# 14-MT7688AN_USB-PCIe.net
KiCad netlist of a schematic drawn in Altium Designer
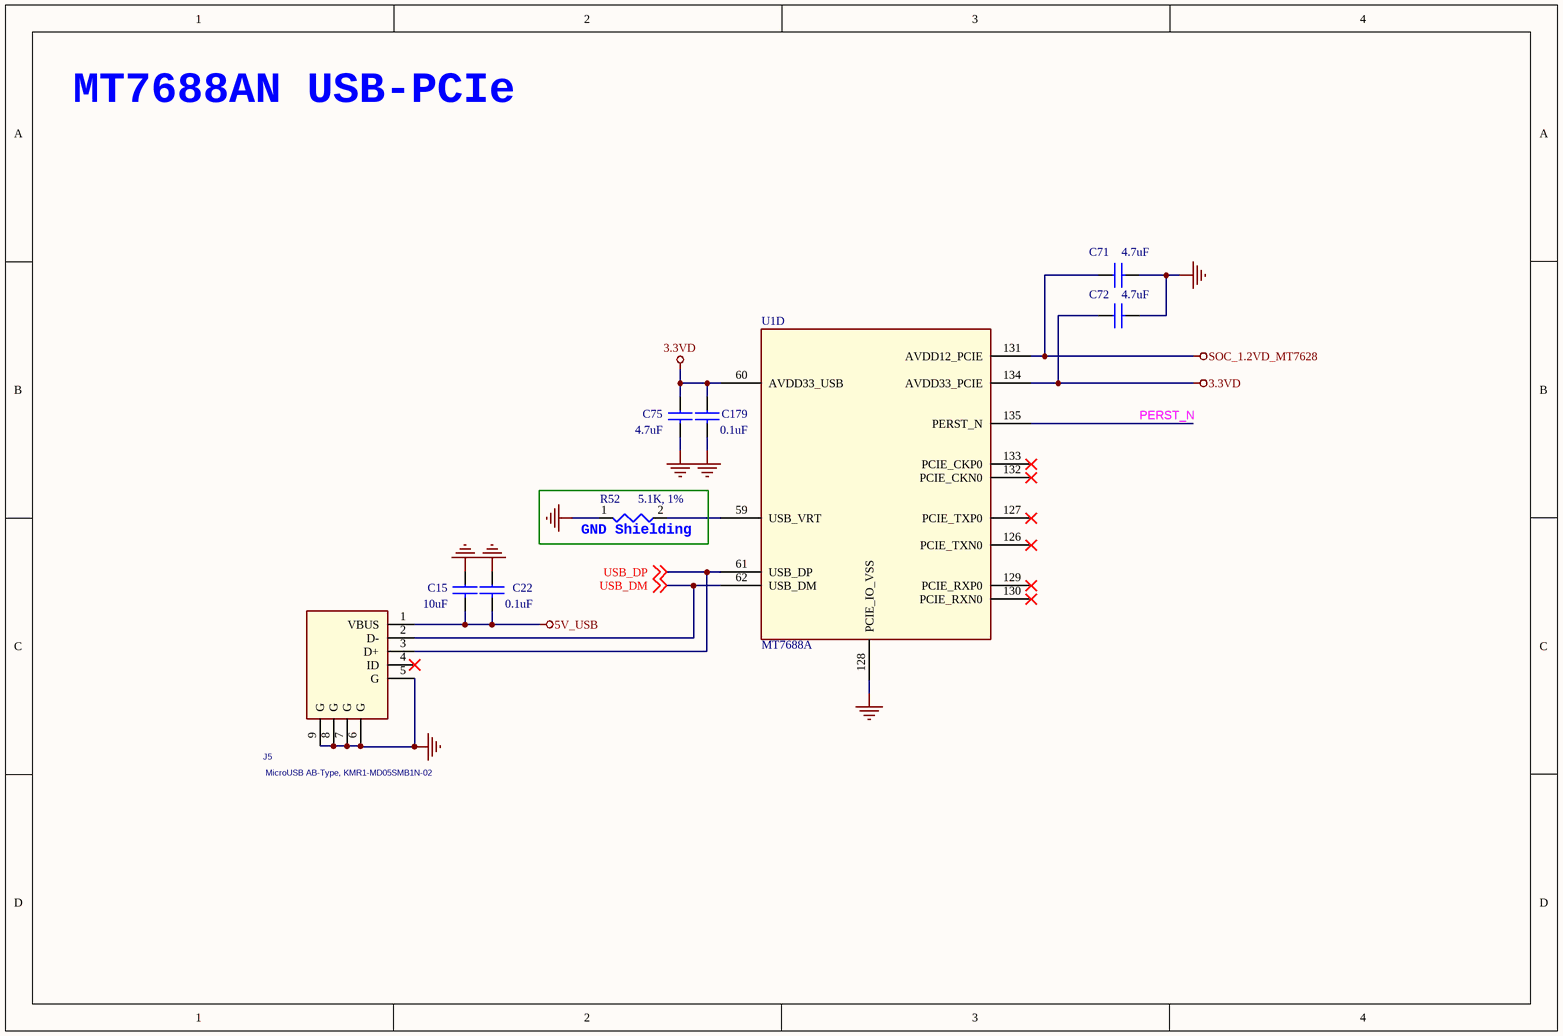
[diagram p0: 14-MT7688AN USB-PCIe.SchDoc]

(export (version "E")
  (design (tool "Eeschema 10.0.6"))
  (components
    (comp (ref "C15")
      (value "10uF")
      (footprint "RLC 0402 M35")
      (libsource (lib "LinkIt Air+ (EK-7688AM+)") (part "CAP NP"))
    )
    (comp (ref "C22")
      (value "0.1uF")
      (footprint "RLC 0201 M35")
      (libsource (lib "LinkIt Air+ (EK-7688AM+)") (part "CAP NP"))
    )
    (comp (ref "C71")
      (value "4.7uF")
      (footprint "RLC 0402 M35")
      (libsource (lib "LinkIt Air+ (EK-7688AM+)") (part "CAP NP"))
    )
    (comp (ref "C72")
      (value "4.7uF")
      (footprint "RLC 0402 M35")
      (libsource (lib "LinkIt Air+ (EK-7688AM+)") (part "CAP NP"))
    )
    (comp (ref "C75")
      (value "4.7uF")
      (footprint "RLC 0402 M35")
      (libsource (lib "LinkIt Air+ (EK-7688AM+)") (part "CAP NP"))
    )
    (comp (ref "C179")
      (value "0.1uF")
      (footprint "RLC 0201 M35")
      (libsource (lib "LinkIt Air+ (EK-7688AM+)") (part "CAP NP"))
    )
    (comp (ref "J5")
      (value "MicroUSB AB-Type, KMR1-MD05SMB1N-02")
      (footprint "MicroUSB-AB")
      (description "MicroUSB AB-Type")
      (fields (field (name "MANUFACTURER") "CUI Inc."))
      (libsource (lib "LinkIt Air+ (EK-7688AM+)") (part "Micro USB TYPE-AB"))
    )
    (comp (ref "R52")
      (value "5.1K, 1%")
      (footprint "RLC 0201 M35")
      (libsource (lib "LinkIt Air+ (EK-7688AM+)") (part "RES/0402_3"))
    )
    (comp (ref "U1")
      (value "MT7688A")
      (footprint "MT7628AN$2F$DRQFN156$2F$SMD$2F$P0.5$2F$12X12")
      (libsource (lib "LinkIt Air+ (EK-7688AM+)") (part "MT7620N-n_26"))
    )
  )
  (nets
    (net (code "1") (name "/PERST_N") (class "Default")
      (node (ref "U1") (pin "135") (pinfunction "PERST_N_135") (pintype "passive"))
    )
    (net (code "2") (name "3.3VD") (class "Default")
      (node (ref "C179") (pin "1") (pinfunction "1_1") (pintype "passive"))
      (node (ref "C72") (pin "1") (pinfunction "1_1") (pintype "passive"))
      (node (ref "C75") (pin "1") (pinfunction "1_1") (pintype "passive"))
      (node (ref "U1") (pin "134") (pinfunction "AVDD33_PCIE_134") (pintype "power_in"))
      (node (ref "U1") (pin "60") (pinfunction "AVDD33_USB_60") (pintype "passive"))
    )
    (net (code "3") (name "5V_USB") (class "Default")
      (node (ref "C15") (pin "2") (pinfunction "2_2") (pintype "passive"))
      (node (ref "C22") (pin "2") (pinfunction "2_2") (pintype "passive"))
      (node (ref "J5") (pin "1") (pinfunction "VBUS_1") (pintype "passive"))
    )
    (net (code "4") (name "GND") (class "Default")
      (node (ref "C15") (pin "1") (pinfunction "1_1") (pintype "passive"))
      (node (ref "C179") (pin "2") (pinfunction "2_2") (pintype "passive"))
      (node (ref "C22") (pin "1") (pinfunction "1_1") (pintype "passive"))
      (node (ref "C71") (pin "2") (pinfunction "2_2") (pintype "passive"))
      (node (ref "C72") (pin "2") (pinfunction "2_2") (pintype "passive"))
      (node (ref "C75") (pin "2") (pinfunction "2_2") (pintype "passive"))
      (node (ref "J5") (pin "5") (pinfunction "G_5") (pintype "passive"))
      (node (ref "J5") (pin "6") (pinfunction "G_6") (pintype "passive"))
      (node (ref "J5") (pin "7") (pinfunction "G_7") (pintype "passive"))
      (node (ref "J5") (pin "8") (pinfunction "G_8") (pintype "passive"))
      (node (ref "J5") (pin "9") (pinfunction "G_9") (pintype "passive"))
      (node (ref "R52") (pin "1") (pinfunction "1_1") (pintype "passive"))
      (node (ref "U1") (pin "128") (pinfunction "PCIE_IO_VSS_128") (pintype "passive"))
    )
    (net (code "5") (name "Net-(U1D-USB_VRT)") (class "Default")
      (node (ref "R52") (pin "2") (pinfunction "2_2") (pintype "passive"))
      (node (ref "U1") (pin "59") (pinfunction "USB_VRT_59") (pintype "passive"))
    )
    (net (code "6") (name "SOC_1.2VD_MT7628") (class "Default")
      (node (ref "C71") (pin "1") (pinfunction "1_1") (pintype "passive"))
      (node (ref "U1") (pin "131") (pinfunction "AVDD12_PCIE_131") (pintype "power_in"))
    )
    (net (code "7") (name "USB_DM") (class "Default")
      (node (ref "J5") (pin "2") (pinfunction "D-_2") (pintype "passive"))
      (node (ref "U1") (pin "62") (pinfunction "USB_DM_62") (pintype "passive"))
    )
    (net (code "8") (name "USB_DP") (class "Default")
      (node (ref "J5") (pin "3") (pinfunction "D+_3") (pintype "passive"))
      (node (ref "U1") (pin "61") (pinfunction "USB_DP_61") (pintype "passive"))
    )
    (net (code "9") (name "unconnected-(J5-ID-Pad4)") (class "Default")
      (node (ref "J5") (pin "4") (pinfunction "ID_4") (pintype "passive+no_connect"))
    )
    (net (code "10") (name "unconnected-(U1D-PCIE_CKN0-Pad132)") (class "Default")
      (node (ref "U1") (pin "132") (pinfunction "PCIE_CKN0_132") (pintype "passive+no_connect"))
    )
    (net (code "11") (name "unconnected-(U1D-PCIE_CKP0-Pad133)") (class "Default")
      (node (ref "U1") (pin "133") (pinfunction "PCIE_CKP0_133") (pintype "passive+no_connect"))
    )
    (net (code "12") (name "unconnected-(U1D-PCIE_RXN0-Pad130)") (class "Default")
      (node (ref "U1") (pin "130") (pinfunction "PCIE_RXN0_130") (pintype "passive+no_connect"))
    )
    (net (code "13") (name "unconnected-(U1D-PCIE_RXP0-Pad129)") (class "Default")
      (node (ref "U1") (pin "129") (pinfunction "PCIE_RXP0_129") (pintype "passive+no_connect"))
    )
    (net (code "14") (name "unconnected-(U1D-PCIE_TXN0-Pad126)") (class "Default")
      (node (ref "U1") (pin "126") (pinfunction "PCIE_TXN0_126") (pintype "passive+no_connect"))
    )
    (net (code "15") (name "unconnected-(U1D-PCIE_TXP0-Pad127)") (class "Default")
      (node (ref "U1") (pin "127") (pinfunction "PCIE_TXP0_127") (pintype "passive+no_connect"))
    )
  )
)
